# HECU_2_0.net
KiCad netlist of a schematic drawn in EAGLE
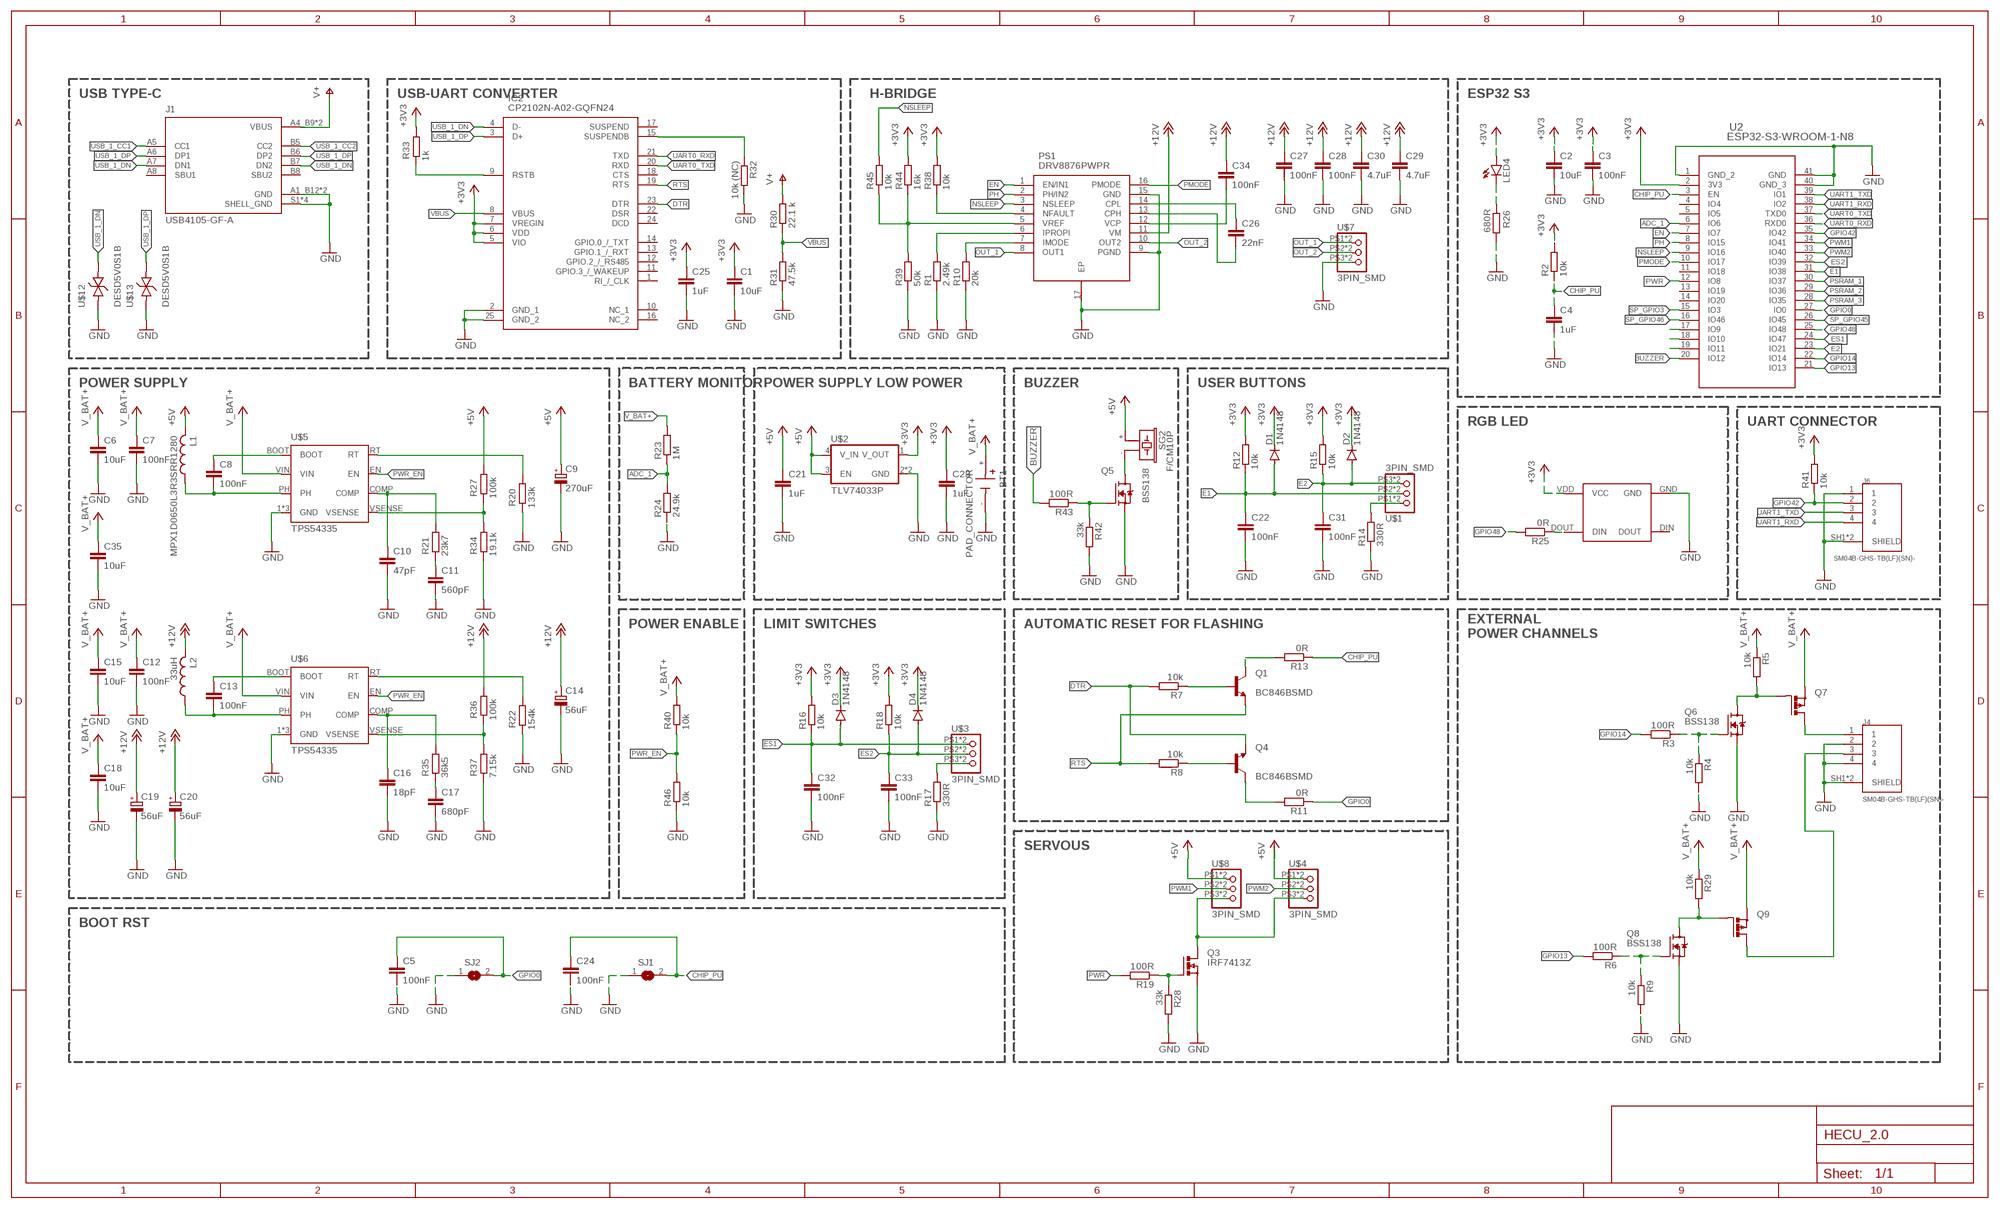
[diagram p0: schematic, sheet 1]

(export (version "E")
  (design (tool "Eeschema 10.0.6"))
  (components
    (comp (ref "BT1")
      (value "PAD_CONNECTOR")
      (footprint "eagle-import:BAT_PADS")
      (libsource (lib "eagle-import") (part "PAD_CONNECTOR"))
    )
    (comp (ref "C1")
      (value "10uF")
      (footprint "eagle-import:C0805")
      (libsource (lib "eagle-import") (part "C-EUC0805"))
    )
    (comp (ref "C2")
      (value "10uF")
      (footprint "eagle-import:C0805")
      (libsource (lib "eagle-import") (part "C-EUC0805"))
    )
    (comp (ref "C3")
      (value "100nF")
      (footprint "eagle-import:C0603")
      (libsource (lib "eagle-import") (part "C-EUC0603"))
    )
    (comp (ref "C4")
      (value "1uF")
      (footprint "eagle-import:C0603")
      (libsource (lib "eagle-import") (part "C-EUC0603"))
    )
    (comp (ref "C5")
      (value "100nF")
      (footprint "eagle-import:C0603")
      (libsource (lib "eagle-import") (part "C-EUC0603"))
    )
    (comp (ref "C6")
      (value "10uF")
      (footprint "eagle-import:C0805")
      (libsource (lib "eagle-import") (part "C-EUC0805"))
    )
    (comp (ref "C7")
      (value "100nF")
      (footprint "eagle-import:C0603")
      (libsource (lib "eagle-import") (part "C-EUC0603"))
    )
    (comp (ref "C8")
      (value "100nF")
      (footprint "eagle-import:C0603")
      (libsource (lib "eagle-import") (part "C-EUC0603"))
    )
    (comp (ref "C9")
      (value "270uF")
      (footprint "eagle-import:PANASONIC_E")
      (libsource (lib "eagle-import") (part "CPOL-EUE"))
    )
    (comp (ref "C10")
      (value "47pF")
      (footprint "eagle-import:C0603")
      (libsource (lib "eagle-import") (part "C-EUC0603"))
    )
    (comp (ref "C11")
      (value "560pF")
      (footprint "eagle-import:C0603")
      (libsource (lib "eagle-import") (part "C-EUC0603"))
    )
    (comp (ref "C12")
      (value "100nF")
      (footprint "eagle-import:C0603")
      (libsource (lib "eagle-import") (part "C-EUC0603"))
    )
    (comp (ref "C13")
      (value "100nF")
      (footprint "eagle-import:C0603")
      (libsource (lib "eagle-import") (part "C-EUC0603"))
    )
    (comp (ref "C14")
      (value "56uF")
      (footprint "eagle-import:PANASONIC_C")
      (libsource (lib "eagle-import") (part "CPOL-EUC"))
    )
    (comp (ref "C15")
      (value "10uF")
      (footprint "eagle-import:C0805")
      (libsource (lib "eagle-import") (part "C-EUC0805"))
    )
    (comp (ref "C16")
      (value "18pF")
      (footprint "eagle-import:C0603")
      (libsource (lib "eagle-import") (part "C-EUC0603"))
    )
    (comp (ref "C17")
      (value "680pF")
      (footprint "eagle-import:C0603")
      (libsource (lib "eagle-import") (part "C-EUC0603"))
    )
    (comp (ref "C18")
      (value "10uF")
      (footprint "eagle-import:C0805")
      (libsource (lib "eagle-import") (part "C-EUC0805"))
    )
    (comp (ref "C19")
      (value "56uF")
      (footprint "eagle-import:PANASONIC_C")
      (libsource (lib "eagle-import") (part "CPOL-EUC"))
    )
    (comp (ref "C20")
      (value "56uF")
      (footprint "eagle-import:PANASONIC_C")
      (libsource (lib "eagle-import") (part "CPOL-EUC"))
    )
    (comp (ref "C21")
      (value "1uF")
      (footprint "eagle-import:C0603")
      (libsource (lib "eagle-import") (part "C-EUC0603"))
    )
    (comp (ref "C22")
      (value "100nF")
      (footprint "eagle-import:C0603")
      (libsource (lib "eagle-import") (part "C-EUC0603"))
    )
    (comp (ref "C23")
      (value "1uF")
      (footprint "eagle-import:C0603")
      (libsource (lib "eagle-import") (part "C-EUC0603"))
    )
    (comp (ref "C24")
      (value "100nF")
      (footprint "eagle-import:C0603")
      (libsource (lib "eagle-import") (part "C-EUC0603"))
    )
    (comp (ref "C25")
      (value "1uF")
      (footprint "eagle-import:C0603")
      (libsource (lib "eagle-import") (part "C-EUC0603"))
    )
    (comp (ref "C26")
      (value "22nF")
      (footprint "eagle-import:C0603")
      (libsource (lib "eagle-import") (part "C-EUC0603"))
    )
    (comp (ref "C27")
      (value "100nF")
      (footprint "eagle-import:C0603")
      (libsource (lib "eagle-import") (part "C-EUC0603"))
    )
    (comp (ref "C28")
      (value "100nF")
      (footprint "eagle-import:C0603")
      (libsource (lib "eagle-import") (part "C-EUC0603"))
    )
    (comp (ref "C29")
      (value "4.7uF")
      (footprint "eagle-import:C0603")
      (libsource (lib "eagle-import") (part "C-EUC0603"))
    )
    (comp (ref "C30")
      (value "4.7uF")
      (footprint "eagle-import:C0603")
      (libsource (lib "eagle-import") (part "C-EUC0603"))
    )
    (comp (ref "C31")
      (value "100nF")
      (footprint "eagle-import:C0603")
      (libsource (lib "eagle-import") (part "C-EUC0603"))
    )
    (comp (ref "C32")
      (value "100nF")
      (footprint "eagle-import:C0603")
      (libsource (lib "eagle-import") (part "C-EUC0603"))
    )
    (comp (ref "C33")
      (value "100nF")
      (footprint "eagle-import:C0603")
      (libsource (lib "eagle-import") (part "C-EUC0603"))
    )
    (comp (ref "C34")
      (value "100nF")
      (footprint "eagle-import:C0603")
      (libsource (lib "eagle-import") (part "C-EUC0603"))
    )
    (comp (ref "C35")
      (value "10uF")
      (footprint "eagle-import:C0805")
      (libsource (lib "eagle-import") (part "C-EUC0805"))
    )
    (comp (ref "D1")
      (value "1N4148")
      (footprint "eagle-import:SOD80C")
      (libsource (lib "eagle-import") (part "1N4148SOD80C"))
    )
    (comp (ref "D2")
      (value "1N4148")
      (footprint "eagle-import:SOD80C")
      (libsource (lib "eagle-import") (part "1N4148SOD80C"))
    )
    (comp (ref "D3")
      (value "1N4148")
      (footprint "eagle-import:SOD80C")
      (libsource (lib "eagle-import") (part "1N4148SOD80C"))
    )
    (comp (ref "D4")
      (value "1N4148")
      (footprint "eagle-import:SOD80C")
      (libsource (lib "eagle-import") (part "1N4148SOD80C"))
    )
    (comp (ref "IC2")
      (value "CP2102N-A02-GQFN24")
      (footprint "eagle-import:QFN50P400X400X80-25N")
      (fields (field (name "MF") "Silicon Labs"))
      (libsource (lib "eagle-import") (part "CP2102N-A02-GQFN24"))
    )
    (comp (ref "J1")
      (value "USB4105-GF-A")
      (footprint "eagle-import:GCT_USB4105-GF-A")
      (fields (field (name "MF") "GCT"))
      (libsource (lib "eagle-import") (part "USB4105-GF-A"))
    )
    (comp (ref "J4")
      (value "SM04B-GHS-TB(LF)(SN)-")
      (footprint "eagle-import:JST_SM04B-GHS-TB(LF)(SN)-")
      (fields (field (name "DIGI-KEY_PART_NUMBER") "455-1566-6-ND") (field (name "MF") "JST Sales"))
      (libsource (lib "eagle-import") (part "SM04B-GHS-TB(LF)(SN)-"))
    )
    (comp (ref "J6")
      (value "SM04B-GHS-TB(LF)(SN)-")
      (footprint "eagle-import:JST_SM04B-GHS-TB(LF)(SN)-")
      (fields (field (name "DIGI-KEY_PART_NUMBER") "455-1566-6-ND") (field (name "MF") "JST Sales"))
      (libsource (lib "eagle-import") (part "SM04B-GHS-TB(LF)(SN)-"))
    )
    (comp (ref "L1")
      (value "MPX1D0650L3R3SRR1280")
      (footprint "eagle-import:COIL_SRR1280")
      (libsource (lib "eagle-import") (part "MPX1D0650L3R3SRR1280"))
    )
    (comp (ref "L2")
      (value "33uH")
      (footprint "eagle-import:COIL_MSS1210")
      (libsource (lib "eagle-import") (part "MPX1D0650L3R3COIL_MSS1210"))
    )
    (comp (ref "LED4")
      (value "LEDCHIPLED_0805")
      (footprint "eagle-import:CHIPLED_0805")
      (libsource (lib "eagle-import") (part "LEDCHIPLED_0805"))
    )
    (comp (ref "PS1")
      (value "DRV8876PWPR")
      (footprint "eagle-import:SOP65P640X120-17N")
      (fields (field (name "MOUSER_PART_NUMBER") "595-DRV8876PWPR"))
      (libsource (lib "eagle-import") (part "DRV8876PWPR"))
    )
    (comp (ref "Q1")
      (value "BC846BSMD")
      (footprint "eagle-import:SOT23")
      (libsource (lib "eagle-import") (part "BC846SMDB"))
    )
    (comp (ref "Q3")
      (value "IRF7413Z")
      (footprint "eagle-import:SO-08")
      (libsource (lib "eagle-import") (part "N-MOSFET-SO8S"))
    )
    (comp (ref "Q4")
      (value "BC846BSMD")
      (footprint "eagle-import:SOT23")
      (libsource (lib "eagle-import") (part "BC846SMDB"))
    )
    (comp (ref "Q5")
      (value "BSS138")
      (footprint "eagle-import:SOT23")
      (fields (field (name "MF") "Fairchild"))
      (libsource (lib "eagle-import") (part "BSS138"))
    )
    (comp (ref "Q6")
      (value "BSS138")
      (footprint "eagle-import:SOT23")
      (fields (field (name "MF") "Fairchild"))
      (libsource (lib "eagle-import") (part "BSS138"))
    )
    (comp (ref "Q7")
      (value "P-MOSFET-SO8")
      (footprint "eagle-import:SO-08")
      (libsource (lib "eagle-import") (part "P-MOSFET-SO8"))
    )
    (comp (ref "Q8")
      (value "BSS138")
      (footprint "eagle-import:SOT23")
      (fields (field (name "MF") "Fairchild"))
      (libsource (lib "eagle-import") (part "BSS138"))
    )
    (comp (ref "Q9")
      (value "P-MOSFET-SO8")
      (footprint "eagle-import:SO-08")
      (libsource (lib "eagle-import") (part "P-MOSFET-SO8"))
    )
    (comp (ref "R1")
      (value "2.49k")
      (footprint "eagle-import:R0603")
      (libsource (lib "eagle-import") (part "R-EU_R0603"))
    )
    (comp (ref "R2")
      (value "10k")
      (footprint "eagle-import:R0603")
      (libsource (lib "eagle-import") (part "R-EU_R0603"))
    )
    (comp (ref "R3")
      (value "100R")
      (footprint "eagle-import:R0603")
      (libsource (lib "eagle-import") (part "R-EU_R0603"))
    )
    (comp (ref "R4")
      (value "10k")
      (footprint "eagle-import:R0603")
      (libsource (lib "eagle-import") (part "R-EU_R0603"))
    )
    (comp (ref "R5")
      (value "10k")
      (footprint "eagle-import:R0603")
      (libsource (lib "eagle-import") (part "R-EU_R0603"))
    )
    (comp (ref "R6")
      (value "100R")
      (footprint "eagle-import:R0603")
      (libsource (lib "eagle-import") (part "R-EU_R0603"))
    )
    (comp (ref "R7")
      (value "10k")
      (footprint "eagle-import:R0603")
      (libsource (lib "eagle-import") (part "R-EU_R0603"))
    )
    (comp (ref "R8")
      (value "10k")
      (footprint "eagle-import:R0603")
      (libsource (lib "eagle-import") (part "R-EU_R0603"))
    )
    (comp (ref "R9")
      (value "10k")
      (footprint "eagle-import:R0603")
      (libsource (lib "eagle-import") (part "R-EU_R0603"))
    )
    (comp (ref "R10")
      (value "20k")
      (footprint "eagle-import:R0603")
      (libsource (lib "eagle-import") (part "R-EU_R0603"))
    )
    (comp (ref "R11")
      (value "0R")
      (footprint "eagle-import:R0603")
      (libsource (lib "eagle-import") (part "R-EU_R0603"))
    )
    (comp (ref "R12")
      (value "10k")
      (footprint "eagle-import:R0603")
      (libsource (lib "eagle-import") (part "R-EU_R0603"))
    )
    (comp (ref "R13")
      (value "0R")
      (footprint "eagle-import:R0603")
      (libsource (lib "eagle-import") (part "R-EU_R0603"))
    )
    (comp (ref "R14")
      (value "330R")
      (footprint "eagle-import:R0603")
      (libsource (lib "eagle-import") (part "R-EU_R0603"))
    )
    (comp (ref "R15")
      (value "10k")
      (footprint "eagle-import:R0603")
      (libsource (lib "eagle-import") (part "R-EU_R0603"))
    )
    (comp (ref "R16")
      (value "10k")
      (footprint "eagle-import:R0603")
      (libsource (lib "eagle-import") (part "R-EU_R0603"))
    )
    (comp (ref "R17")
      (value "330R")
      (footprint "eagle-import:R0603")
      (libsource (lib "eagle-import") (part "R-EU_R0603"))
    )
    (comp (ref "R18")
      (value "10k")
      (footprint "eagle-import:R0603")
      (libsource (lib "eagle-import") (part "R-EU_R0603"))
    )
    (comp (ref "R19")
      (value "100R")
      (footprint "eagle-import:R0603")
      (libsource (lib "eagle-import") (part "R-EU_R0603"))
    )
    (comp (ref "R20")
      (value "133k")
      (footprint "eagle-import:R0603")
      (libsource (lib "eagle-import") (part "R-EU_R0603"))
    )
    (comp (ref "R21")
      (value "23k7")
      (footprint "eagle-import:R0603")
      (libsource (lib "eagle-import") (part "R-EU_R0603"))
    )
    (comp (ref "R22")
      (value "154k")
      (footprint "eagle-import:R0603")
      (libsource (lib "eagle-import") (part "R-EU_R0603"))
    )
    (comp (ref "R23")
      (value "1M")
      (footprint "eagle-import:R0603")
      (libsource (lib "eagle-import") (part "R-EU_R0603"))
    )
    (comp (ref "R24")
      (value "24.9k")
      (footprint "eagle-import:R0603")
      (libsource (lib "eagle-import") (part "R-EU_R0603"))
    )
    (comp (ref "R25")
      (value "0R")
      (footprint "eagle-import:R0603")
      (libsource (lib "eagle-import") (part "R-EU_R0603"))
    )
    (comp (ref "R26")
      (value "680R")
      (footprint "eagle-import:R0603")
      (libsource (lib "eagle-import") (part "R-EU_R0603"))
    )
    (comp (ref "R27")
      (value "100k")
      (footprint "eagle-import:R0603")
      (libsource (lib "eagle-import") (part "R-EU_R0603"))
    )
    (comp (ref "R28")
      (value "33k")
      (footprint "eagle-import:R0603")
      (libsource (lib "eagle-import") (part "R-EU_R0603"))
    )
    (comp (ref "R29")
      (value "10k")
      (footprint "eagle-import:R0603")
      (libsource (lib "eagle-import") (part "R-EU_R0603"))
    )
    (comp (ref "R30")
      (value "22.1 k")
      (footprint "eagle-import:R0603")
      (libsource (lib "eagle-import") (part "R-EU_R0603"))
    )
    (comp (ref "R31")
      (value "47.5k")
      (footprint "eagle-import:R0603")
      (libsource (lib "eagle-import") (part "R-EU_R0603"))
    )
    (comp (ref "R32")
      (value "10k (NC)")
      (footprint "eagle-import:R0603")
      (libsource (lib "eagle-import") (part "R-EU_R0603"))
    )
    (comp (ref "R33")
      (value "1k")
      (footprint "eagle-import:R0603")
      (libsource (lib "eagle-import") (part "R-EU_R0603"))
    )
    (comp (ref "R34")
      (value "19.1k")
      (footprint "eagle-import:R0603")
      (libsource (lib "eagle-import") (part "R-EU_R0603"))
    )
    (comp (ref "R35")
      (value "36k5")
      (footprint "eagle-import:R0603")
      (libsource (lib "eagle-import") (part "R-EU_R0603"))
    )
    (comp (ref "R36")
      (value "100k")
      (footprint "eagle-import:R0603")
      (libsource (lib "eagle-import") (part "R-EU_R0603"))
    )
    (comp (ref "R37")
      (value "7.15k")
      (footprint "eagle-import:R0603")
      (libsource (lib "eagle-import") (part "R-EU_R0603"))
    )
    (comp (ref "R38")
      (value "10k")
      (footprint "eagle-import:R0603")
      (libsource (lib "eagle-import") (part "R-EU_R0603"))
    )
    (comp (ref "R39")
      (value "50k")
      (footprint "eagle-import:R0603")
      (libsource (lib "eagle-import") (part "R-EU_R0603"))
    )
    (comp (ref "R40")
      (value "10k")
      (footprint "eagle-import:R0603")
      (libsource (lib "eagle-import") (part "R-EU_R0603"))
    )
    (comp (ref "R41")
      (value "10k")
      (footprint "eagle-import:R0603")
      (libsource (lib "eagle-import") (part "R-EU_R0603"))
    )
    (comp (ref "R42")
      (value "33k")
      (footprint "eagle-import:R0603")
      (libsource (lib "eagle-import") (part "R-EU_R0603"))
    )
    (comp (ref "R43")
      (value "100R")
      (footprint "eagle-import:R0603")
      (libsource (lib "eagle-import") (part "R-EU_R0603"))
    )
    (comp (ref "R44")
      (value "16k")
      (footprint "eagle-import:R0603")
      (libsource (lib "eagle-import") (part "R-EU_R0603"))
    )
    (comp (ref "R45")
      (value "10k")
      (footprint "eagle-import:R0603")
      (libsource (lib "eagle-import") (part "R-EU_R0603"))
    )
    (comp (ref "R46")
      (value "10k")
      (footprint "eagle-import:R0603")
      (libsource (lib "eagle-import") (part "R-EU_R0603"))
    )
    (comp (ref "RGB1")
      (value "SK6812MINI")
      (footprint "eagle-import:2020REVMNT")
      (fields (field (name "MF") "DONGGUANG OPSCO OPTOELECTRONICS CO., LTD"))
      (libsource (lib "eagle-import") (part "SK6812MINI"))
    )
    (comp (ref "SG2")
      (value "F/CM10P")
      (footprint "eagle-import:F_CM10P")
      (libsource (lib "eagle-import") (part "F/CM10P"))
    )
    (comp (ref "SJ1") (value "SJ") (footprint "eagle-import:SJ") (libsource (lib "eagle-import") (part "SJ")))
    (comp (ref "SJ2") (value "SJ") (footprint "eagle-import:SJ") (libsource (lib "eagle-import") (part "SJ")))
    (comp (ref "U$1")
      (value "3PIN_SMD")
      (footprint "eagle-import:3PIN_PAD")
      (libsource (lib "eagle-import") (part "3PIN_SMD"))
    )
    (comp (ref "U$2")
      (value "TLV74033P")
      (footprint "eagle-import:SUP_TPS3831L30DQNR")
      (libsource (lib "eagle-import") (part "TLV74033P"))
    )
    (comp (ref "U$3")
      (value "3PIN_SMD")
      (footprint "eagle-import:3PIN_PAD")
      (libsource (lib "eagle-import") (part "3PIN_SMD"))
    )
    (comp (ref "U$4")
      (value "3PIN_SMD")
      (footprint "eagle-import:3PIN_PAD")
      (libsource (lib "eagle-import") (part "3PIN_SMD"))
    )
    (comp (ref "U$5")
      (value "TPS54335")
      (footprint "eagle-import:DDA0008E_L")
      (libsource (lib "eagle-import") (part "TPS54325"))
    )
    (comp (ref "U$6")
      (value "TPS54335")
      (footprint "eagle-import:DDA0008E_L")
      (libsource (lib "eagle-import") (part "TPS54325"))
    )
    (comp (ref "U$7")
      (value "3PIN_SMD")
      (footprint "eagle-import:3PIN_PAD")
      (libsource (lib "eagle-import") (part "3PIN_SMD"))
    )
    (comp (ref "U$8")
      (value "3PIN_SMD")
      (footprint "eagle-import:3PIN_PAD")
      (libsource (lib "eagle-import") (part "3PIN_SMD"))
    )
    (comp (ref "U$12")
      (value "DESD5V0S1B")
      (footprint "eagle-import:DIO_BAS316_RRG")
      (libsource (lib "eagle-import") (part "DESD5V0S1B"))
    )
    (comp (ref "U$13")
      (value "DESD5V0S1B")
      (footprint "eagle-import:DIO_BAS316_RRG")
      (libsource (lib "eagle-import") (part "DESD5V0S1B"))
    )
    (comp (ref "U2")
      (value "ESP32-S3-WROOM-1-N8")
      (footprint "eagle-import:ESP32-S3-WROOM-1-N8_EXP")
      (fields (field (name "COPYRIGHT") "Copyright (C) 2022 Ultra Librarian. All rights reserved."))
      (libsource (lib "eagle-import") (part "ESP32-S3-WROOM-1-N8"))
    )
  )
  (nets
    (net (code "1") (name "+3V3") (class "Default")
      (node (ref "C1") (pin "1") (pinfunction "1_1") (pintype "passive"))
      (node (ref "C2") (pin "1") (pinfunction "1_1") (pintype "passive"))
      (node (ref "C23") (pin "1") (pinfunction "1_1") (pintype "passive"))
      (node (ref "C25") (pin "1") (pinfunction "1_1") (pintype "passive"))
      (node (ref "C3") (pin "1") (pinfunction "1_1") (pintype "passive"))
      (node (ref "D1") (pin "C") (pinfunction "C_C") (pintype "passive"))
      (node (ref "D2") (pin "C") (pinfunction "C_C") (pintype "passive"))
      (node (ref "D3") (pin "C") (pinfunction "C_C") (pintype "passive"))
      (node (ref "D4") (pin "C") (pinfunction "C_C") (pintype "passive"))
      (node (ref "IC2") (pin "5") (pinfunction "VIO_5") (pintype "power_in"))
      (node (ref "IC2") (pin "6") (pinfunction "VDD_6") (pintype "power_in"))
      (node (ref "IC2") (pin "7") (pinfunction "VREGIN_7") (pintype "power_in"))
      (node (ref "LED4") (pin "A") (pinfunction "A_A") (pintype "passive"))
      (node (ref "R12") (pin "2") (pinfunction "2_2") (pintype "passive"))
      (node (ref "R15") (pin "2") (pinfunction "2_2") (pintype "passive"))
      (node (ref "R16") (pin "2") (pinfunction "2_2") (pintype "passive"))
      (node (ref "R18") (pin "2") (pinfunction "2_2") (pintype "passive"))
      (node (ref "R2") (pin "2") (pinfunction "2_2") (pintype "passive"))
      (node (ref "R33") (pin "1") (pinfunction "1_1") (pintype "passive"))
      (node (ref "R38") (pin "2") (pinfunction "2_2") (pintype "passive"))
      (node (ref "R41") (pin "2") (pinfunction "2_2") (pintype "passive"))
      (node (ref "R44") (pin "2") (pinfunction "2_2") (pintype "passive"))
      (node (ref "RGB1") (pin "VDD") (pinfunction "VCC_VDD") (pintype "bidirectional"))
      (node (ref "U$2") (pin "1") (pinfunction "V_OUT_1") (pintype "output"))
      (node (ref "U2") (pin "2") (pinfunction "3V3_2") (pintype "power_in"))
    )
    (net (code "2") (name "+5V") (class "Default")
      (node (ref "C21") (pin "1") (pinfunction "1_1") (pintype "passive"))
      (node (ref "C9") (pin "+") (pinfunction "+_+") (pintype "passive"))
      (node (ref "L1") (pin "2") (pinfunction "2_2") (pintype "passive"))
      (node (ref "R27") (pin "1") (pinfunction "1_1") (pintype "passive"))
      (node (ref "SG2") (pin "+") (pinfunction "1_+") (pintype "passive"))
      (node (ref "U$2") (pin "3") (pinfunction "EN_3") (pintype "input"))
      (node (ref "U$2") (pin "4") (pinfunction "V_IN_4") (pintype "input"))
      (node (ref "U$4") (pin "P$1") (pinfunction "1_P$1") (pintype "passive"))
      (node (ref "U$4") (pin "P$4") (pinfunction "1_P$4") (pintype "passive"))
      (node (ref "U$8") (pin "P$1") (pinfunction "1_P$1") (pintype "passive"))
      (node (ref "U$8") (pin "P$4") (pinfunction "1_P$4") (pintype "passive"))
    )
    (net (code "3") (name "+12V") (class "Default")
      (node (ref "C14") (pin "+") (pinfunction "+_+") (pintype "passive"))
      (node (ref "C19") (pin "+") (pinfunction "+_+") (pintype "passive"))
      (node (ref "C20") (pin "+") (pinfunction "+_+") (pintype "passive"))
      (node (ref "C27") (pin "1") (pinfunction "1_1") (pintype "passive"))
      (node (ref "C28") (pin "1") (pinfunction "1_1") (pintype "passive"))
      (node (ref "C29") (pin "1") (pinfunction "1_1") (pintype "passive"))
      (node (ref "C30") (pin "1") (pinfunction "1_1") (pintype "passive"))
      (node (ref "C34") (pin "1") (pinfunction "1_1") (pintype "passive"))
      (node (ref "L2") (pin "2") (pinfunction "2_2") (pintype "passive"))
      (node (ref "PS1") (pin "11") (pinfunction "VM_11") (pintype "bidirectional"))
      (node (ref "R36") (pin "1") (pinfunction "1_1") (pintype "passive"))
    )
    (net (code "4") (name "ADC_1") (class "Default")
      (node (ref "R23") (pin "1") (pinfunction "1_1") (pintype "passive"))
      (node (ref "R24") (pin "2") (pinfunction "2_2") (pintype "passive"))
      (node (ref "U2") (pin "6") (pinfunction "IO6_6") (pintype "bidirectional"))
    )
    (net (code "5") (name "BUZZER") (class "Default")
      (node (ref "R43") (pin "2") (pinfunction "2_2") (pintype "passive"))
      (node (ref "U2") (pin "20") (pinfunction "IO12_20") (pintype "bidirectional"))
    )
    (net (code "6") (name "CHIP_PU") (class "Default")
      (node (ref "C24") (pin "1") (pinfunction "1_1") (pintype "passive"))
      (node (ref "C4") (pin "1") (pinfunction "1_1") (pintype "passive"))
      (node (ref "R13") (pin "1") (pinfunction "1_1") (pintype "passive"))
      (node (ref "R2") (pin "1") (pinfunction "1_1") (pintype "passive"))
      (node (ref "SJ1") (pin "2") (pinfunction "2_2") (pintype "passive"))
      (node (ref "U2") (pin "3") (pinfunction "EN_3") (pintype "input"))
    )
    (net (code "7") (name "DTR") (class "Default")
      (node (ref "IC2") (pin "23") (pinfunction "DTR_23") (pintype "bidirectional"))
      (node (ref "Q4") (pin "2") (pinfunction "E_2") (pintype "passive"))
      (node (ref "R7") (pin "2") (pinfunction "2_2") (pintype "passive"))
    )
    (net (code "8") (name "E1") (class "Default")
      (node (ref "C22") (pin "1") (pinfunction "1_1") (pintype "passive"))
      (node (ref "D1") (pin "A") (pinfunction "A_A") (pintype "passive"))
      (node (ref "R12") (pin "1") (pinfunction "1_1") (pintype "passive"))
      (node (ref "U$1") (pin "P$2") (pinfunction "2_P$2") (pintype "passive"))
      (node (ref "U$1") (pin "P$5") (pinfunction "2_P$5") (pintype "passive"))
      (node (ref "U2") (pin "31") (pinfunction "IO38_31") (pintype "bidirectional"))
    )
    (net (code "9") (name "E2") (class "Default")
      (node (ref "C31") (pin "1") (pinfunction "1_1") (pintype "passive"))
      (node (ref "D2") (pin "A") (pinfunction "A_A") (pintype "passive"))
      (node (ref "R15") (pin "1") (pinfunction "1_1") (pintype "passive"))
      (node (ref "U$1") (pin "P$3") (pinfunction "3_P$3") (pintype "passive"))
      (node (ref "U$1") (pin "P$6") (pinfunction "3_P$6") (pintype "passive"))
      (node (ref "U2") (pin "23") (pinfunction "IO21_23") (pintype "bidirectional"))
    )
    (net (code "10") (name "EN") (class "Default")
      (node (ref "PS1") (pin "1") (pinfunction "EN/IN1_1") (pintype "bidirectional"))
      (node (ref "U2") (pin "7") (pinfunction "IO7_7") (pintype "bidirectional"))
    )
    (net (code "11") (name "ES1") (class "Default")
      (node (ref "C32") (pin "1") (pinfunction "1_1") (pintype "passive"))
      (node (ref "D3") (pin "A") (pinfunction "A_A") (pintype "passive"))
      (node (ref "R16") (pin "1") (pinfunction "1_1") (pintype "passive"))
      (node (ref "U$3") (pin "P$1") (pinfunction "1_P$1") (pintype "passive"))
      (node (ref "U$3") (pin "P$4") (pinfunction "1_P$4") (pintype "passive"))
      (node (ref "U2") (pin "24") (pinfunction "IO47_24") (pintype "bidirectional"))
    )
    (net (code "12") (name "ES2") (class "Default")
      (node (ref "C33") (pin "1") (pinfunction "1_1") (pintype "passive"))
      (node (ref "D4") (pin "A") (pinfunction "A_A") (pintype "passive"))
      (node (ref "R18") (pin "1") (pinfunction "1_1") (pintype "passive"))
      (node (ref "U$3") (pin "P$2") (pinfunction "2_P$2") (pintype "passive"))
      (node (ref "U$3") (pin "P$5") (pinfunction "2_P$5") (pintype "passive"))
      (node (ref "U2") (pin "32") (pinfunction "IO39_32") (pintype "bidirectional"))
    )
    (net (code "13") (name "GND") (class "Default")
      (node (ref "BT1") (pin "-") (pinfunction "-_-") (pintype "passive"))
      (node (ref "C1") (pin "2") (pinfunction "2_2") (pintype "passive"))
      (node (ref "C10") (pin "2") (pinfunction "2_2") (pintype "passive"))
      (node (ref "C11") (pin "2") (pinfunction "2_2") (pintype "passive"))
      (node (ref "C12") (pin "2") (pinfunction "2_2") (pintype "passive"))
      (node (ref "C14") (pin "-") (pinfunction "-_-") (pintype "passive"))
      (node (ref "C15") (pin "2") (pinfunction "2_2") (pintype "passive"))
      (node (ref "C16") (pin "2") (pinfunction "2_2") (pintype "passive"))
      (node (ref "C17") (pin "2") (pinfunction "2_2") (pintype "passive"))
      (node (ref "C18") (pin "2") (pinfunction "2_2") (pintype "passive"))
      (node (ref "C19") (pin "-") (pinfunction "-_-") (pintype "passive"))
      (node (ref "C2") (pin "2") (pinfunction "2_2") (pintype "passive"))
      (node (ref "C20") (pin "-") (pinfunction "-_-") (pintype "passive"))
      (node (ref "C21") (pin "2") (pinfunction "2_2") (pintype "passive"))
      (node (ref "C22") (pin "2") (pinfunction "2_2") (pintype "passive"))
      (node (ref "C23") (pin "2") (pinfunction "2_2") (pintype "passive"))
      (node (ref "C24") (pin "2") (pinfunction "2_2") (pintype "passive"))
      (node (ref "C25") (pin "2") (pinfunction "2_2") (pintype "passive"))
      (node (ref "C27") (pin "2") (pinfunction "2_2") (pintype "passive"))
      (node (ref "C28") (pin "2") (pinfunction "2_2") (pintype "passive"))
      (node (ref "C29") (pin "2") (pinfunction "2_2") (pintype "passive"))
      (node (ref "C3") (pin "2") (pinfunction "2_2") (pintype "passive"))
      (node (ref "C30") (pin "2") (pinfunction "2_2") (pintype "passive"))
      (node (ref "C31") (pin "2") (pinfunction "2_2") (pintype "passive"))
      (node (ref "C32") (pin "2") (pinfunction "2_2") (pintype "passive"))
      (node (ref "C33") (pin "2") (pinfunction "2_2") (pintype "passive"))
      (node (ref "C35") (pin "2") (pinfunction "2_2") (pintype "passive"))
      (node (ref "C4") (pin "2") (pinfunction "2_2") (pintype "passive"))
      (node (ref "C5") (pin "2") (pinfunction "2_2") (pintype "passive"))
      (node (ref "C6") (pin "2") (pinfunction "2_2") (pintype "passive"))
      (node (ref "C7") (pin "2") (pinfunction "2_2") (pintype "passive"))
      (node (ref "C9") (pin "-") (pinfunction "-_-") (pintype "passive"))
      (node (ref "IC2") (pin "2") (pinfunction "GND_1_2") (pintype "power_in"))
      (node (ref "IC2") (pin "25") (pinfunction "GND_2_25") (pintype "power_in"))
      (node (ref "J1") (pin "A1_B12") (pinfunction "GND_A1_B12") (pintype "power_in"))
      (node (ref "J1") (pin "B1_A12") (pinfunction "GND_B1_A12") (pintype "power_in"))
      (node (ref "J1") (pin "S1") (pinfunction "SHELL_GND_S1") (pintype "power_in"))
      (node (ref "J1") (pin "S2") (pinfunction "SHELL_GND_S2") (pintype "power_in"))
      (node (ref "J1") (pin "S3") (pinfunction "SHELL_GND_S3") (pintype "power_in"))
      (node (ref "J1") (pin "S4") (pinfunction "SHELL_GND_S4") (pintype "power_in"))
      (node (ref "J4") (pin "2") (pinfunction "2_2") (pintype "passive"))
      (node (ref "J4") (pin "4") (pinfunction "4_4") (pintype "passive"))
      (node (ref "J4") (pin "SH1") (pinfunction "SHIELD_SH1") (pintype "power_in"))
      (node (ref "J4") (pin "SH2") (pinfunction "SHIELD_SH2") (pintype "power_in"))
      (node (ref "J6") (pin "1") (pinfunction "1_1") (pintype "passive"))
      (node (ref "J6") (pin "SH1") (pinfunction "SHIELD_SH1") (pintype "power_in"))
      (node (ref "J6") (pin "SH2") (pinfunction "SHIELD_SH2") (pintype "power_in"))
      (node (ref "PS1") (pin "15") (pinfunction "GND_15") (pintype "bidirectional"))
      (node (ref "PS1") (pin "17") (pinfunction "EP_17") (pintype "bidirectional"))
      (node (ref "PS1") (pin "9") (pinfunction "PGND_9") (pintype "bidirectional"))
      (node (ref "Q3") (pin "1") (pinfunction "S_1") (pintype "passive"))
      (node (ref "Q3") (pin "2") (pinfunction "S_2") (pintype "passive"))
      (node (ref "Q3") (pin "3") (pinfunction "S_3") (pintype "passive"))
      (node (ref "Q5") (pin "2") (pinfunction "S_2") (pintype "passive"))
      (node (ref "Q6") (pin "2") (pinfunction "S_2") (pintype "passive"))
      (node (ref "Q8") (pin "2") (pinfunction "S_2") (pintype "passive"))
      (node (ref "R1") (pin "1") (pinfunction "1_1") (pintype "passive"))
      (node (ref "R10") (pin "1") (pinfunction "1_1") (pintype "passive"))
      (node (ref "R14") (pin "1") (pinfunction "1_1") (pintype "passive"))
      (node (ref "R17") (pin "1") (pinfunction "1_1") (pintype "passive"))
      (node (ref "R20") (pin "2") (pinfunction "2_2") (pintype "passive"))
      (node (ref "R22") (pin "2") (pinfunction "2_2") (pintype "passive"))
      (node (ref "R24") (pin "1") (pinfunction "1_1") (pintype "passive"))
      (node (ref "R26") (pin "1") (pinfunction "1_1") (pintype "passive"))
      (node (ref "R28") (pin "2") (pinfunction "2_2") (pintype "passive"))
      (node (ref "R31") (pin "1") (pinfunction "1_1") (pintype "passive"))
      (node (ref "R32") (pin "2") (pinfunction "2_2") (pintype "passive"))
      (node (ref "R34") (pin "2") (pinfunction "2_2") (pintype "passive"))
      (node (ref "R37") (pin "2") (pinfunction "2_2") (pintype "passive"))
      (node (ref "R39") (pin "1") (pinfunction "1_1") (pintype "passive"))
      (node (ref "R4") (pin "2") (pinfunction "2_2") (pintype "passive"))
      (node (ref "R42") (pin "2") (pinfunction "2_2") (pintype "passive"))
      (node (ref "R46") (pin "1") (pinfunction "1_1") (pintype "passive"))
      (node (ref "R9") (pin "2") (pinfunction "2_2") (pintype "passive"))
      (node (ref "RGB1") (pin "GND") (pinfunction "GND_GND") (pintype "bidirectional"))
      (node (ref "SJ1") (pin "1") (pinfunction "1_1") (pintype "passive"))
      (node (ref "SJ2") (pin "1") (pinfunction "1_1") (pintype "passive"))
      (node (ref "U$12") (pin "A") (pinfunction "1_A") (pintype "passive"))
      (node (ref "U$13") (pin "A") (pinfunction "1_A") (pintype "passive"))
      (node (ref "U$2") (pin "2") (pinfunction "GND_2") (pintype "input"))
      (node (ref "U$2") (pin "5") (pinfunction "GND_5") (pintype "input"))
      (node (ref "U$5") (pin "1") (pinfunction "GND_1") (pintype "output"))
      (node (ref "U$5") (pin "9") (pinfunction "GND_9") (pintype "output"))
      (node (ref "U$5") (pin "GND") (pinfunction "GND_GND") (pintype "output"))
      (node (ref "U$6") (pin "1") (pinfunction "GND_1") (pintype "output"))
      (node (ref "U$6") (pin "9") (pinfunction "GND_9") (pintype "output"))
      (node (ref "U$6") (pin "GND") (pinfunction "GND_GND") (pintype "output"))
      (node (ref "U$7") (pin "P$3") (pinfunction "3_P$3") (pintype "passive"))
      (node (ref "U$7") (pin "P$6") (pinfunction "3_P$6") (pintype "passive"))
      (node (ref "U2") (pin "1") (pinfunction "GND_2_1") (pintype "passive"))
      (node (ref "U2") (pin "40") (pinfunction "GND_3_40") (pintype "passive"))
      (node (ref "U2") (pin "41") (pinfunction "GND_41") (pintype "passive"))
    )
    (net (code "14") (name "GPIO0") (class "Default")
      (node (ref "C5") (pin "1") (pinfunction "1_1") (pintype "passive"))
      (node (ref "R11") (pin "1") (pinfunction "1_1") (pintype "passive"))
      (node (ref "SJ2") (pin "2") (pinfunction "2_2") (pintype "passive"))
      (node (ref "U2") (pin "27") (pinfunction "IO0_27") (pintype "bidirectional"))
    )
    (net (code "15") (name "GPIO13") (class "Default")
      (node (ref "R6") (pin "2") (pinfunction "2_2") (pintype "passive"))
      (node (ref "U2") (pin "21") (pinfunction "IO13_21") (pintype "bidirectional"))
    )
    (net (code "16") (name "GPIO14") (class "Default")
      (node (ref "R3") (pin "2") (pinfunction "2_2") (pintype "passive"))
      (node (ref "U2") (pin "22") (pinfunction "IO14_22") (pintype "bidirectional"))
    )
    (net (code "17") (name "GPIO42") (class "Default")
      (node (ref "J6") (pin "2") (pinfunction "2_2") (pintype "passive"))
      (node (ref "R41") (pin "1") (pinfunction "1_1") (pintype "passive"))
      (node (ref "U2") (pin "35") (pinfunction "IO42_35") (pintype "bidirectional"))
    )
    (net (code "18") (name "GPIO48") (class "Default")
      (node (ref "R25") (pin "2") (pinfunction "2_2") (pintype "passive"))
      (node (ref "U2") (pin "25") (pinfunction "IO48_25") (pintype "bidirectional"))
    )
    (net (code "19") (name "NSLEEP") (class "Default")
      (node (ref "PS1") (pin "3") (pinfunction "NSLEEP_3") (pintype "bidirectional"))
      (node (ref "R45") (pin "2") (pinfunction "2_2") (pintype "passive"))
      (node (ref "U2") (pin "9") (pinfunction "IO16_9") (pintype "bidirectional"))
    )
    (net (code "20") (name "Net-(C8-Pad1)") (class "Default")
      (node (ref "C8") (pin "1") (pinfunction "1_1") (pintype "passive"))
      (node (ref "U$5") (pin "BOOT") (pinfunction "BOOT_BOOT") (pintype "input"))
    )
    (net (code "21") (name "Net-(C8-Pad2)") (class "Default")
      (node (ref "C8") (pin "2") (pinfunction "2_2") (pintype "passive"))
      (node (ref "L1") (pin "1") (pinfunction "1_1") (pintype "passive"))
      (node (ref "U$5") (pin "PH") (pinfunction "PH_PH") (pintype "input"))
    )
    (net (code "22") (name "Net-(C10-Pad1)") (class "Default")
      (node (ref "C10") (pin "1") (pinfunction "1_1") (pintype "passive"))
      (node (ref "R21") (pin "1") (pinfunction "1_1") (pintype "passive"))
      (node (ref "U$5") (pin "COMP") (pinfunction "COMP_COMP") (pintype "input"))
    )
    (net (code "23") (name "Net-(C11-Pad1)") (class "Default")
      (node (ref "C11") (pin "1") (pinfunction "1_1") (pintype "passive"))
      (node (ref "R21") (pin "2") (pinfunction "2_2") (pintype "passive"))
    )
    (net (code "24") (name "Net-(C13-Pad1)") (class "Default")
      (node (ref "C13") (pin "1") (pinfunction "1_1") (pintype "passive"))
      (node (ref "U$6") (pin "BOOT") (pinfunction "BOOT_BOOT") (pintype "input"))
    )
    (net (code "25") (name "Net-(C13-Pad2)") (class "Default")
      (node (ref "C13") (pin "2") (pinfunction "2_2") (pintype "passive"))
      (node (ref "L2") (pin "1") (pinfunction "1_1") (pintype "passive"))
      (node (ref "U$6") (pin "PH") (pinfunction "PH_PH") (pintype "input"))
    )
    (net (code "26") (name "Net-(C16-Pad1)") (class "Default")
      (node (ref "C16") (pin "1") (pinfunction "1_1") (pintype "passive"))
      (node (ref "R35") (pin "1") (pinfunction "1_1") (pintype "passive"))
      (node (ref "U$6") (pin "COMP") (pinfunction "COMP_COMP") (pintype "input"))
    )
    (net (code "27") (name "Net-(C17-Pad1)") (class "Default")
      (node (ref "C17") (pin "1") (pinfunction "1_1") (pintype "passive"))
      (node (ref "R35") (pin "2") (pinfunction "2_2") (pintype "passive"))
    )
    (net (code "28") (name "Net-(IC2-RSTB)") (class "Default")
      (node (ref "IC2") (pin "9") (pinfunction "RSTB_9") (pintype "bidirectional"))
      (node (ref "R33") (pin "2") (pinfunction "2_2") (pintype "passive"))
    )
    (net (code "29") (name "Net-(IC2-SUSPENDB)") (class "Default")
      (node (ref "IC2") (pin "15") (pinfunction "SUSPENDB_15") (pintype "output"))
      (node (ref "R32") (pin "1") (pinfunction "1_1") (pintype "passive"))
    )
    (net (code "30") (name "Net-(J4-Pad1)") (class "Default")
      (node (ref "J4") (pin "1") (pinfunction "1_1") (pintype "passive"))
      (node (ref "Q7") (pin "5") (pinfunction "D_5") (pintype "passive"))
      (node (ref "Q7") (pin "6") (pinfunction "D_6") (pintype "passive"))
      (node (ref "Q7") (pin "7") (pinfunction "D_7") (pintype "passive"))
      (node (ref "Q7") (pin "8") (pinfunction "D_8") (pintype "passive"))
    )
    (net (code "31") (name "Net-(J4-Pad3)") (class "Default")
      (node (ref "J4") (pin "3") (pinfunction "3_3") (pintype "passive"))
      (node (ref "Q9") (pin "5") (pinfunction "D_5") (pintype "passive"))
      (node (ref "Q9") (pin "6") (pinfunction "D_6") (pintype "passive"))
      (node (ref "Q9") (pin "7") (pinfunction "D_7") (pintype "passive"))
      (node (ref "Q9") (pin "8") (pinfunction "D_8") (pintype "passive"))
    )
    (net (code "32") (name "Net-(LED4-PadC)") (class "Default")
      (node (ref "LED4") (pin "C") (pinfunction "C_C") (pintype "passive"))
      (node (ref "R26") (pin "2") (pinfunction "2_2") (pintype "passive"))
    )
    (net (code "33") (name "Net-(PS1-CPH)") (class "Default")
      (node (ref "C26") (pin "2") (pinfunction "2_2") (pintype "passive"))
      (node (ref "PS1") (pin "13") (pinfunction "CPH_13") (pintype "bidirectional"))
    )
    (net (code "34") (name "Net-(PS1-CPL)") (class "Default")
      (node (ref "C26") (pin "1") (pinfunction "1_1") (pintype "passive"))
      (node (ref "PS1") (pin "14") (pinfunction "CPL_14") (pintype "bidirectional"))
    )
    (net (code "35") (name "Net-(PS1-IMODE)") (class "Default")
      (node (ref "PS1") (pin "7") (pinfunction "IMODE_7") (pintype "bidirectional"))
      (node (ref "R10") (pin "2") (pinfunction "2_2") (pintype "passive"))
    )
    (net (code "36") (name "Net-(PS1-IPROPI)") (class "Default")
      (node (ref "PS1") (pin "6") (pinfunction "IPROPI_6") (pintype "bidirectional"))
      (node (ref "R1") (pin "2") (pinfunction "2_2") (pintype "passive"))
    )
    (net (code "37") (name "Net-(PS1-NFAULT)") (class "Default")
      (node (ref "PS1") (pin "4") (pinfunction "NFAULT_4") (pintype "bidirectional"))
      (node (ref "R38") (pin "1") (pinfunction "1_1") (pintype "passive"))
    )
    (net (code "38") (name "Net-(PS1-VCP)") (class "Default")
      (node (ref "C34") (pin "2") (pinfunction "2_2") (pintype "passive"))
      (node (ref "PS1") (pin "12") (pinfunction "VCP_12") (pintype "bidirectional"))
    )
    (net (code "39") (name "Net-(PS1-VREF)") (class "Default")
      (node (ref "PS1") (pin "5") (pinfunction "VREF_5") (pintype "bidirectional"))
      (node (ref "R39") (pin "2") (pinfunction "2_2") (pintype "passive"))
      (node (ref "R44") (pin "1") (pinfunction "1_1") (pintype "passive"))
      (node (ref "R45") (pin "1") (pinfunction "1_1") (pintype "passive"))
    )
    (net (code "40") (name "Net-(Q1-B)") (class "Default")
      (node (ref "Q1") (pin "1") (pinfunction "B_1") (pintype "passive"))
      (node (ref "R7") (pin "1") (pinfunction "1_1") (pintype "passive"))
    )
    (net (code "41") (name "Net-(Q1-C)") (class "Default")
      (node (ref "Q1") (pin "3") (pinfunction "C_3") (pintype "passive"))
      (node (ref "R13") (pin "2") (pinfunction "2_2") (pintype "passive"))
    )
    (net (code "42") (name "Net-(Q3-D-Pad5)") (class "Default")
      (node (ref "Q3") (pin "5") (pinfunction "D_5") (pintype "passive"))
      (node (ref "Q3") (pin "6") (pinfunction "D_6") (pintype "passive"))
      (node (ref "Q3") (pin "7") (pinfunction "D_7") (pintype "passive"))
      (node (ref "Q3") (pin "8") (pinfunction "D_8") (pintype "passive"))
      (node (ref "U$4") (pin "P$3") (pinfunction "3_P$3") (pintype "passive"))
      (node (ref "U$4") (pin "P$6") (pinfunction "3_P$6") (pintype "passive"))
      (node (ref "U$8") (pin "P$3") (pinfunction "3_P$3") (pintype "passive"))
      (node (ref "U$8") (pin "P$6") (pinfunction "3_P$6") (pintype "passive"))
    )
    (net (code "43") (name "Net-(Q3-G)") (class "Default")
      (node (ref "Q3") (pin "4") (pinfunction "G_4") (pintype "passive"))
      (node (ref "R19") (pin "1") (pinfunction "1_1") (pintype "passive"))
      (node (ref "R28") (pin "1") (pinfunction "1_1") (pintype "passive"))
    )
    (net (code "44") (name "Net-(Q4-B)") (class "Default")
      (node (ref "Q4") (pin "1") (pinfunction "B_1") (pintype "passive"))
      (node (ref "R8") (pin "1") (pinfunction "1_1") (pintype "passive"))
    )
    (net (code "45") (name "Net-(Q4-C)") (class "Default")
      (node (ref "Q4") (pin "3") (pinfunction "C_3") (pintype "passive"))
      (node (ref "R11") (pin "2") (pinfunction "2_2") (pintype "passive"))
    )
    (net (code "46") (name "Net-(Q5-D)") (class "Default")
      (node (ref "Q5") (pin "3") (pinfunction "D_3") (pintype "passive"))
      (node (ref "SG2") (pin "-") (pinfunction "2_-") (pintype "passive"))
    )
    (net (code "47") (name "Net-(Q5-G)") (class "Default")
      (node (ref "Q5") (pin "1") (pinfunction "G_1") (pintype "passive"))
      (node (ref "R42") (pin "1") (pinfunction "1_1") (pintype "passive"))
      (node (ref "R43") (pin "1") (pinfunction "1_1") (pintype "passive"))
    )
    (net (code "48") (name "Net-(Q6-D)") (class "Default")
      (node (ref "Q6") (pin "3") (pinfunction "D_3") (pintype "passive"))
      (node (ref "Q7") (pin "4") (pinfunction "G_4") (pintype "passive"))
      (node (ref "R5") (pin "2") (pinfunction "2_2") (pintype "passive"))
    )
    (net (code "49") (name "Net-(Q6-G)") (class "Default")
      (node (ref "Q6") (pin "1") (pinfunction "G_1") (pintype "passive"))
      (node (ref "R3") (pin "1") (pinfunction "1_1") (pintype "passive"))
      (node (ref "R4") (pin "1") (pinfunction "1_1") (pintype "passive"))
    )
    (net (code "50") (name "Net-(Q8-D)") (class "Default")
      (node (ref "Q8") (pin "3") (pinfunction "D_3") (pintype "passive"))
      (node (ref "Q9") (pin "4") (pinfunction "G_4") (pintype "passive"))
      (node (ref "R29") (pin "2") (pinfunction "2_2") (pintype "passive"))
    )
    (net (code "51") (name "Net-(Q8-G)") (class "Default")
      (node (ref "Q8") (pin "1") (pinfunction "G_1") (pintype "passive"))
      (node (ref "R6") (pin "1") (pinfunction "1_1") (pintype "passive"))
      (node (ref "R9") (pin "1") (pinfunction "1_1") (pintype "passive"))
    )
    (net (code "52") (name "Net-(R14-Pad2)") (class "Default")
      (node (ref "R14") (pin "2") (pinfunction "2_2") (pintype "passive"))
      (node (ref "U$1") (pin "P$1") (pinfunction "1_P$1") (pintype "passive"))
      (node (ref "U$1") (pin "P$4") (pinfunction "1_P$4") (pintype "passive"))
    )
    (net (code "53") (name "Net-(R17-Pad2)") (class "Default")
      (node (ref "R17") (pin "2") (pinfunction "2_2") (pintype "passive"))
      (node (ref "U$3") (pin "P$3") (pinfunction "3_P$3") (pintype "passive"))
      (node (ref "U$3") (pin "P$6") (pinfunction "3_P$6") (pintype "passive"))
    )
    (net (code "54") (name "Net-(R20-Pad1)") (class "Default")
      (node (ref "R20") (pin "1") (pinfunction "1_1") (pintype "passive"))
      (node (ref "U$5") (pin "RT") (pinfunction "RT_RT") (pintype "input"))
    )
    (net (code "55") (name "Net-(R22-Pad1)") (class "Default")
      (node (ref "R22") (pin "1") (pinfunction "1_1") (pintype "passive"))
      (node (ref "U$6") (pin "RT") (pinfunction "RT_RT") (pintype "input"))
    )
    (net (code "56") (name "Net-(R27-Pad2)") (class "Default")
      (node (ref "R27") (pin "2") (pinfunction "2_2") (pintype "passive"))
      (node (ref "R34") (pin "1") (pinfunction "1_1") (pintype "passive"))
      (node (ref "U$5") (pin "VSENSE") (pinfunction "VSENSE_VSENSE") (pintype "power_in"))
    )
    (net (code "57") (name "Net-(R36-Pad2)") (class "Default")
      (node (ref "R36") (pin "2") (pinfunction "2_2") (pintype "passive"))
      (node (ref "R37") (pin "1") (pinfunction "1_1") (pintype "passive"))
      (node (ref "U$6") (pin "VSENSE") (pinfunction "VSENSE_VSENSE") (pintype "power_in"))
    )
    (net (code "58") (name "Net-(RGB1-DIN)") (class "Default")
      (node (ref "R25") (pin "1") (pinfunction "1_1") (pintype "passive"))
      (node (ref "RGB1") (pin "DOUT") (pinfunction "DIN_DOUT") (pintype "bidirectional"))
    )
    (net (code "59") (name "OUT_1") (class "Default")
      (node (ref "PS1") (pin "8") (pinfunction "OUT1_8") (pintype "bidirectional"))
      (node (ref "U$7") (pin "P$1") (pinfunction "1_P$1") (pintype "passive"))
      (node (ref "U$7") (pin "P$4") (pinfunction "1_P$4") (pintype "passive"))
    )
    (net (code "60") (name "OUT_2") (class "Default")
      (node (ref "PS1") (pin "10") (pinfunction "OUT2_10") (pintype "bidirectional"))
      (node (ref "U$7") (pin "P$2") (pinfunction "2_P$2") (pintype "passive"))
      (node (ref "U$7") (pin "P$5") (pinfunction "2_P$5") (pintype "passive"))
    )
    (net (code "61") (name "PH") (class "Default")
      (node (ref "PS1") (pin "2") (pinfunction "PH/IN2_2") (pintype "bidirectional"))
      (node (ref "U2") (pin "8") (pinfunction "IO15_8") (pintype "bidirectional"))
    )
    (net (code "62") (name "PMODE") (class "Default")
      (node (ref "PS1") (pin "16") (pinfunction "PMODE_16") (pintype "bidirectional"))
      (node (ref "U2") (pin "10") (pinfunction "IO17_10") (pintype "bidirectional"))
    )
    (net (code "63") (name "PSRAM_1") (class "Default")
      (node (ref "U2") (pin "30") (pinfunction "IO37_30") (pintype "bidirectional"))
    )
    (net (code "64") (name "PSRAM_2") (class "Default")
      (node (ref "U2") (pin "29") (pinfunction "IO36_29") (pintype "bidirectional"))
    )
    (net (code "65") (name "PSRAM_3") (class "Default")
      (node (ref "U2") (pin "28") (pinfunction "IO35_28") (pintype "bidirectional"))
    )
    (net (code "66") (name "PWM1") (class "Default")
      (node (ref "U$8") (pin "P$2") (pinfunction "2_P$2") (pintype "passive"))
      (node (ref "U$8") (pin "P$5") (pinfunction "2_P$5") (pintype "passive"))
      (node (ref "U2") (pin "34") (pinfunction "IO41_34") (pintype "bidirectional"))
    )
    (net (code "67") (name "PWM2") (class "Default")
      (node (ref "U$4") (pin "P$2") (pinfunction "2_P$2") (pintype "passive"))
      (node (ref "U$4") (pin "P$5") (pinfunction "2_P$5") (pintype "passive"))
      (node (ref "U2") (pin "33") (pinfunction "IO40_33") (pintype "bidirectional"))
    )
    (net (code "68") (name "PWR") (class "Default")
      (node (ref "R19") (pin "2") (pinfunction "2_2") (pintype "passive"))
      (node (ref "U2") (pin "12") (pinfunction "IO8_12") (pintype "bidirectional"))
    )
    (net (code "69") (name "PWR_EN") (class "Default")
      (node (ref "R40") (pin "1") (pinfunction "1_1") (pintype "passive"))
      (node (ref "R46") (pin "2") (pinfunction "2_2") (pintype "passive"))
      (node (ref "U$5") (pin "EN") (pinfunction "EN_EN") (pintype "passive"))
      (node (ref "U$6") (pin "EN") (pinfunction "EN_EN") (pintype "passive"))
    )
    (net (code "70") (name "RTS") (class "Default")
      (node (ref "IC2") (pin "19") (pinfunction "RTS_19") (pintype "output"))
      (node (ref "Q1") (pin "2") (pinfunction "E_2") (pintype "passive"))
      (node (ref "R8") (pin "2") (pinfunction "2_2") (pintype "passive"))
    )
    (net (code "71") (name "SP_GPIO3") (class "Default")
      (node (ref "U2") (pin "15") (pinfunction "IO3_15") (pintype "bidirectional"))
    )
    (net (code "72") (name "SP_GPIO45") (class "Default")
      (node (ref "U2") (pin "26") (pinfunction "IO45_26") (pintype "bidirectional"))
    )
    (net (code "73") (name "SP_GPIO46") (class "Default")
      (node (ref "U2") (pin "16") (pinfunction "IO46_16") (pintype "bidirectional"))
    )
    (net (code "74") (name "UART0_RXD") (class "Default")
      (node (ref "IC2") (pin "21") (pinfunction "TXD_21") (pintype "output"))
      (node (ref "U2") (pin "36") (pinfunction "RXD0_36") (pintype "bidirectional"))
    )
    (net (code "75") (name "UART0_TXD") (class "Default")
      (node (ref "IC2") (pin "20") (pinfunction "RXD_20") (pintype "input"))
      (node (ref "U2") (pin "37") (pinfunction "TXD0_37") (pintype "bidirectional"))
    )
    (net (code "76") (name "UART1_RXD") (class "Default")
      (node (ref "J6") (pin "4") (pinfunction "4_4") (pintype "passive"))
      (node (ref "U2") (pin "38") (pinfunction "IO2_38") (pintype "bidirectional"))
    )
    (net (code "77") (name "UART1_TXD") (class "Default")
      (node (ref "J6") (pin "3") (pinfunction "3_3") (pintype "passive"))
      (node (ref "U2") (pin "39") (pinfunction "IO1_39") (pintype "bidirectional"))
    )
    (net (code "78") (name "USB_1_CC1") (class "Default")
      (node (ref "J1") (pin "A5") (pinfunction "CC1_A5") (pintype "bidirectional"))
    )
    (net (code "79") (name "USB_1_CC2") (class "Default")
      (node (ref "J1") (pin "B5") (pinfunction "CC2_B5") (pintype "bidirectional"))
    )
    (net (code "80") (name "USB_1_DN") (class "Default")
      (node (ref "IC2") (pin "4") (pinfunction "D-_4") (pintype "bidirectional"))
      (node (ref "J1") (pin "A7") (pinfunction "DN1_A7") (pintype "bidirectional"))
      (node (ref "J1") (pin "B7") (pinfunction "DN2_B7") (pintype "bidirectional"))
      (node (ref "U$12") (pin "C") (pinfunction "2_C") (pintype "passive"))
    )
    (net (code "81") (name "USB_1_DP") (class "Default")
      (node (ref "IC2") (pin "3") (pinfunction "D+_3") (pintype "bidirectional"))
      (node (ref "J1") (pin "A6") (pinfunction "DP1_A6") (pintype "bidirectional"))
      (node (ref "J1") (pin "B6") (pinfunction "DP2_B6") (pintype "bidirectional"))
      (node (ref "U$13") (pin "C") (pinfunction "2_C") (pintype "passive"))
    )
    (net (code "82") (name "V+") (class "Default")
      (node (ref "J1") (pin "A4_B9") (pinfunction "VBUS_A4_B9") (pintype "power_in"))
      (node (ref "J1") (pin "B4_A9") (pinfunction "VBUS_B4_A9") (pintype "power_in"))
      (node (ref "R30") (pin "2") (pinfunction "2_2") (pintype "passive"))
    )
    (net (code "83") (name "VBUS") (class "Default")
      (node (ref "IC2") (pin "8") (pinfunction "VBUS_8") (pintype "power_in"))
      (node (ref "R30") (pin "1") (pinfunction "1_1") (pintype "passive"))
      (node (ref "R31") (pin "2") (pinfunction "2_2") (pintype "passive"))
    )
    (net (code "84") (name "V_BAT+") (class "Default")
      (node (ref "BT1") (pin "+") (pinfunction "+_+") (pintype "passive"))
      (node (ref "C12") (pin "1") (pinfunction "1_1") (pintype "passive"))
      (node (ref "C15") (pin "1") (pinfunction "1_1") (pintype "passive"))
      (node (ref "C18") (pin "1") (pinfunction "1_1") (pintype "passive"))
      (node (ref "C35") (pin "1") (pinfunction "1_1") (pintype "passive"))
      (node (ref "C6") (pin "1") (pinfunction "1_1") (pintype "passive"))
      (node (ref "C7") (pin "1") (pinfunction "1_1") (pintype "passive"))
      (node (ref "Q7") (pin "1") (pinfunction "S_1") (pintype "passive"))
      (node (ref "Q7") (pin "2") (pinfunction "S_2") (pintype "passive"))
      (node (ref "Q7") (pin "3") (pinfunction "S_3") (pintype "passive"))
      (node (ref "Q9") (pin "1") (pinfunction "S_1") (pintype "passive"))
      (node (ref "Q9") (pin "2") (pinfunction "S_2") (pintype "passive"))
      (node (ref "Q9") (pin "3") (pinfunction "S_3") (pintype "passive"))
      (node (ref "R23") (pin "2") (pinfunction "2_2") (pintype "passive"))
      (node (ref "R29") (pin "1") (pinfunction "1_1") (pintype "passive"))
      (node (ref "R40") (pin "2") (pinfunction "2_2") (pintype "passive"))
      (node (ref "R5") (pin "1") (pinfunction "1_1") (pintype "passive"))
      (node (ref "U$5") (pin "VIN") (pinfunction "VIN_VIN") (pintype "input"))
      (node (ref "U$6") (pin "VIN") (pinfunction "VIN_VIN") (pintype "input"))
    )
    (net (code "85") (name "unconnected-(IC2-CTS-Pad18)") (class "Default")
      (node (ref "IC2") (pin "18") (pinfunction "CTS_18") (pintype "bidirectional"))
    )
    (net (code "86") (name "unconnected-(IC2-DCD-Pad24)") (class "Default")
      (node (ref "IC2") (pin "24") (pinfunction "DCD_24") (pintype "bidirectional"))
    )
    (net (code "87") (name "unconnected-(IC2-DSR-Pad22)") (class "Default")
      (node (ref "IC2") (pin "22") (pinfunction "DSR_22") (pintype "bidirectional"))
    )
    (net (code "88") (name "unconnected-(IC2-GPIO.0_{slash}_TXT-Pad14)") (class "Default")
      (node (ref "IC2") (pin "14") (pinfunction "GPIO.0_/_TXT_14") (pintype "bidirectional"))
    )
    (net (code "89") (name "unconnected-(IC2-GPIO.1_{slash}_RXT-Pad13)") (class "Default")
      (node (ref "IC2") (pin "13") (pinfunction "GPIO.1_/_RXT_13") (pintype "bidirectional"))
    )
    (net (code "90") (name "unconnected-(IC2-GPIO.2_{slash}_RS485-Pad12)") (class "Default")
      (node (ref "IC2") (pin "12") (pinfunction "GPIO.2_/_RS485_12") (pintype "bidirectional"))
    )
    (net (code "91") (name "unconnected-(IC2-GPIO.3_{slash}_WAKEUP-Pad11)") (class "Default")
      (node (ref "IC2") (pin "11") (pinfunction "GPIO.3_/_WAKEUP_11") (pintype "bidirectional"))
    )
    (net (code "92") (name "unconnected-(IC2-NC_1-Pad10)") (class "Default")
      (node (ref "IC2") (pin "10") (pinfunction "NC_1_10") (pintype "no_connect"))
    )
    (net (code "93") (name "unconnected-(IC2-NC_2-Pad16)") (class "Default")
      (node (ref "IC2") (pin "16") (pinfunction "NC_2_16") (pintype "no_connect"))
    )
    (net (code "94") (name "unconnected-(IC2-RI_{slash}_CLK-Pad1)") (class "Default")
      (node (ref "IC2") (pin "1") (pinfunction "RI_/_CLK_1") (pintype "bidirectional"))
    )
    (net (code "95") (name "unconnected-(IC2-SUSPEND-Pad17)") (class "Default")
      (node (ref "IC2") (pin "17") (pinfunction "SUSPEND_17") (pintype "output"))
    )
    (net (code "96") (name "unconnected-(J1-SBU1-PadA8)") (class "Default")
      (node (ref "J1") (pin "A8") (pinfunction "SBU1_A8") (pintype "bidirectional"))
    )
    (net (code "97") (name "unconnected-(J1-SBU2-PadB8)") (class "Default")
      (node (ref "J1") (pin "B8") (pinfunction "SBU2_B8") (pintype "bidirectional"))
    )
    (net (code "98") (name "unconnected-(RGB1-DOUT-PadDIN)") (class "Default")
      (node (ref "RGB1") (pin "DIN") (pinfunction "DOUT_DIN") (pintype "bidirectional"))
    )
    (net (code "99") (name "unconnected-(U2-IO4-Pad4)") (class "Default")
      (node (ref "U2") (pin "4") (pinfunction "IO4_4") (pintype "bidirectional"))
    )
    (net (code "100") (name "unconnected-(U2-IO5-Pad5)") (class "Default")
      (node (ref "U2") (pin "5") (pinfunction "IO5_5") (pintype "bidirectional"))
    )
    (net (code "101") (name "unconnected-(U2-IO9-Pad17)") (class "Default")
      (node (ref "U2") (pin "17") (pinfunction "IO9_17") (pintype "bidirectional"))
    )
    (net (code "102") (name "unconnected-(U2-IO10-Pad18)") (class "Default")
      (node (ref "U2") (pin "18") (pinfunction "IO10_18") (pintype "bidirectional"))
    )
    (net (code "103") (name "unconnected-(U2-IO11-Pad19)") (class "Default")
      (node (ref "U2") (pin "19") (pinfunction "IO11_19") (pintype "bidirectional"))
    )
    (net (code "104") (name "unconnected-(U2-IO18-Pad11)") (class "Default")
      (node (ref "U2") (pin "11") (pinfunction "IO18_11") (pintype "bidirectional"))
    )
    (net (code "105") (name "unconnected-(U2-IO19-Pad13)") (class "Default")
      (node (ref "U2") (pin "13") (pinfunction "IO19_13") (pintype "bidirectional"))
    )
    (net (code "106") (name "unconnected-(U2-IO20-Pad14)") (class "Default")
      (node (ref "U2") (pin "14") (pinfunction "IO20_14") (pintype "bidirectional"))
    )
  )
)
